# GarageMote.net
KiCad netlist of a schematic drawn in EAGLE
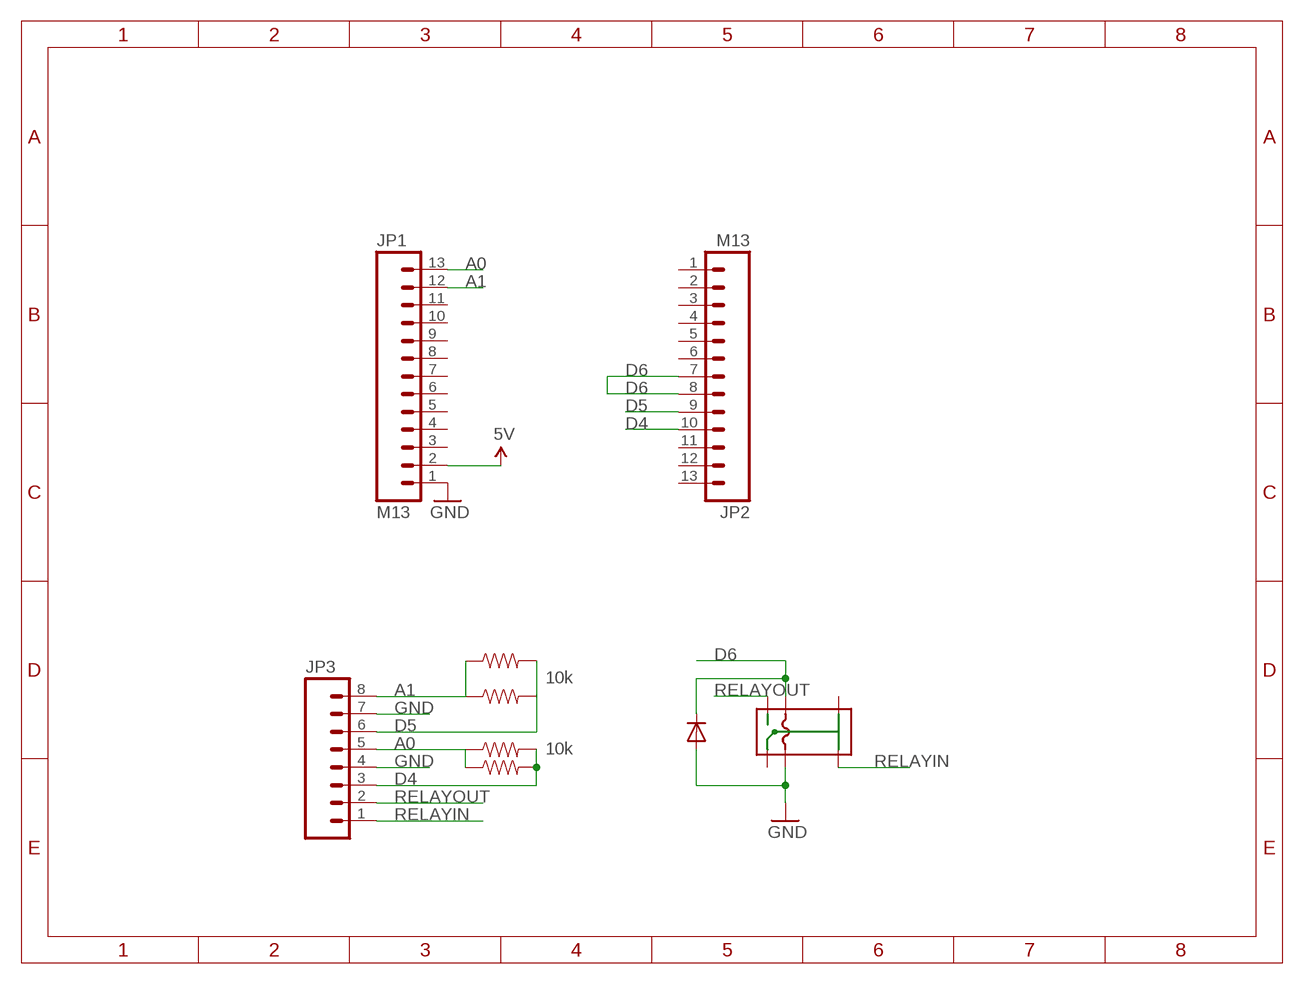
[diagram p0: schematic, sheet 1]

(export (version "E")
  (design (tool "Eeschema 10.0.6"))
  (components
    (comp (ref "1N4001")
      (value "DIODEUPRIGHT")
      (footprint "eagle-import:DIODE_UPRIGHT")
      (libsource (lib "eagle-import") (part "DIODEUPRIGHT"))
    )
    (comp (ref "JP1")
      (value "M13")
      (footprint "eagle-import:1X13")
      (libsource (lib "eagle-import") (part "M13"))
    )
    (comp (ref "JP2")
      (value "M13")
      (footprint "eagle-import:1X13")
      (libsource (lib "eagle-import") (part "M13"))
    )
    (comp (ref "JP3")
      (value "M081X08")
      (footprint "eagle-import:1X08")
      (libsource (lib "eagle-import") (part "M081X08"))
    )
    (comp (ref "JRC-2F")
      (value "JRC-23F")
      (footprint "eagle-import:JRC-23F")
      (libsource (lib "eagle-import") (part "JRC-23F"))
    )
    (comp (ref "R1")
      (value "10k")
      (footprint "eagle-import:0603-RES")
      (libsource (lib "eagle-import") (part "RESISTOR0603-RES"))
    )
    (comp (ref "R2")
      (value "10k")
      (footprint "eagle-import:0603-RES")
      (libsource (lib "eagle-import") (part "RESISTOR0603-RES"))
    )
    (comp (ref "R3")
      (value "RESISTOR1/4W")
      (footprint "eagle-import:AXIAL-1_4W")
      (libsource (lib "eagle-import") (part "RESISTOR1/4W"))
    )
    (comp (ref "R4")
      (value "RESISTOR1/4W")
      (footprint "eagle-import:AXIAL-1_4W")
      (libsource (lib "eagle-import") (part "RESISTOR1/4W"))
    )
  )
  (nets
    (net (code "1") (name "/A0") (class "Default")
      (node (ref "JP1") (pin "13") (pinfunction "13_13") (pintype "passive"))
      (node (ref "JP3") (pin "5") (pinfunction "5_5") (pintype "passive"))
      (node (ref "R1") (pin "1") (pinfunction "1_1") (pintype "passive"))
      (node (ref "R3") (pin "P$1") (pinfunction "1_P$1") (pintype "passive"))
    )
    (net (code "2") (name "/A1") (class "Default")
      (node (ref "JP1") (pin "12") (pinfunction "12_12") (pintype "passive"))
      (node (ref "JP3") (pin "8") (pinfunction "8_8") (pintype "passive"))
      (node (ref "R2") (pin "1") (pinfunction "1_1") (pintype "passive"))
      (node (ref "R4") (pin "P$1") (pinfunction "1_P$1") (pintype "passive"))
    )
    (net (code "3") (name "/D4") (class "Default")
      (node (ref "JP2") (pin "10") (pinfunction "10_10") (pintype "passive"))
      (node (ref "JP3") (pin "3") (pinfunction "3_3") (pintype "passive"))
      (node (ref "R1") (pin "2") (pinfunction "2_2") (pintype "passive"))
      (node (ref "R3") (pin "P$2") (pinfunction "2_P$2") (pintype "passive"))
    )
    (net (code "4") (name "/D5") (class "Default")
      (node (ref "JP2") (pin "9") (pinfunction "9_9") (pintype "passive"))
      (node (ref "JP3") (pin "6") (pinfunction "6_6") (pintype "passive"))
      (node (ref "R2") (pin "2") (pinfunction "2_2") (pintype "passive"))
      (node (ref "R4") (pin "P$2") (pinfunction "2_P$2") (pintype "passive"))
    )
    (net (code "5") (name "/D6") (class "Default")
      (node (ref "1N4001") (pin "CATHODE_MINUS") (pinfunction "CATHODE_MINUS_CATHODE_MINUS") (pintype "passive"))
      (node (ref "JP2") (pin "7") (pinfunction "7_7") (pintype "passive"))
      (node (ref "JP2") (pin "8") (pinfunction "8_8") (pintype "passive"))
      (node (ref "JRC-2F") (pin "COIL1") (pinfunction "COIL1_COIL1") (pintype "bidirectional"))
    )
    (net (code "6") (name "/RELAYIN") (class "Default")
      (node (ref "JP3") (pin "1") (pinfunction "1_1") (pintype "passive"))
      (node (ref "JRC-2F") (pin "COM2") (pinfunction "COM2_COM2") (pintype "bidirectional"))
    )
    (net (code "7") (name "/RELAYOUT") (class "Default")
      (node (ref "JP3") (pin "2") (pinfunction "2_2") (pintype "passive"))
      (node (ref "JRC-2F") (pin "SW1") (pinfunction "SW1_SW1") (pintype "bidirectional"))
    )
    (net (code "8") (name "5V") (class "Default")
      (node (ref "JP1") (pin "2") (pinfunction "2_2") (pintype "passive"))
    )
    (net (code "9") (name "GND") (class "Default")
      (node (ref "1N4001") (pin "ANODE_PLUS") (pinfunction "ANODE_PLUS_ANODE_PLUS") (pintype "passive"))
      (node (ref "JP1") (pin "1") (pinfunction "1_1") (pintype "passive"))
      (node (ref "JP3") (pin "4") (pinfunction "4_4") (pintype "passive"))
      (node (ref "JP3") (pin "7") (pinfunction "7_7") (pintype "passive"))
      (node (ref "JRC-2F") (pin "COIL2") (pinfunction "COIL2_COIL2") (pintype "bidirectional"))
    )
    (net (code "10") (name "unconnected-(JP1-Pad3)") (class "Default")
      (node (ref "JP1") (pin "3") (pinfunction "3_3") (pintype "passive"))
    )
    (net (code "11") (name "unconnected-(JP1-Pad4)") (class "Default")
      (node (ref "JP1") (pin "4") (pinfunction "4_4") (pintype "passive"))
    )
    (net (code "12") (name "unconnected-(JP1-Pad5)") (class "Default")
      (node (ref "JP1") (pin "5") (pinfunction "5_5") (pintype "passive"))
    )
    (net (code "13") (name "unconnected-(JP1-Pad6)") (class "Default")
      (node (ref "JP1") (pin "6") (pinfunction "6_6") (pintype "passive"))
    )
    (net (code "14") (name "unconnected-(JP1-Pad7)") (class "Default")
      (node (ref "JP1") (pin "7") (pinfunction "7_7") (pintype "passive"))
    )
    (net (code "15") (name "unconnected-(JP1-Pad8)") (class "Default")
      (node (ref "JP1") (pin "8") (pinfunction "8_8") (pintype "passive"))
    )
    (net (code "16") (name "unconnected-(JP1-Pad9)") (class "Default")
      (node (ref "JP1") (pin "9") (pinfunction "9_9") (pintype "passive"))
    )
    (net (code "17") (name "unconnected-(JP1-Pad10)") (class "Default")
      (node (ref "JP1") (pin "10") (pinfunction "10_10") (pintype "passive"))
    )
    (net (code "18") (name "unconnected-(JP1-Pad11)") (class "Default")
      (node (ref "JP1") (pin "11") (pinfunction "11_11") (pintype "passive"))
    )
    (net (code "19") (name "unconnected-(JP2-Pad1)") (class "Default")
      (node (ref "JP2") (pin "1") (pinfunction "1_1") (pintype "passive"))
    )
    (net (code "20") (name "unconnected-(JP2-Pad2)") (class "Default")
      (node (ref "JP2") (pin "2") (pinfunction "2_2") (pintype "passive"))
    )
    (net (code "21") (name "unconnected-(JP2-Pad3)") (class "Default")
      (node (ref "JP2") (pin "3") (pinfunction "3_3") (pintype "passive"))
    )
    (net (code "22") (name "unconnected-(JP2-Pad4)") (class "Default")
      (node (ref "JP2") (pin "4") (pinfunction "4_4") (pintype "passive"))
    )
    (net (code "23") (name "unconnected-(JP2-Pad5)") (class "Default")
      (node (ref "JP2") (pin "5") (pinfunction "5_5") (pintype "passive"))
    )
    (net (code "24") (name "unconnected-(JP2-Pad6)") (class "Default")
      (node (ref "JP2") (pin "6") (pinfunction "6_6") (pintype "passive"))
    )
    (net (code "25") (name "unconnected-(JP2-Pad11)") (class "Default")
      (node (ref "JP2") (pin "11") (pinfunction "11_11") (pintype "passive"))
    )
    (net (code "26") (name "unconnected-(JP2-Pad12)") (class "Default")
      (node (ref "JP2") (pin "12") (pinfunction "12_12") (pintype "passive"))
    )
    (net (code "27") (name "unconnected-(JP2-Pad13)") (class "Default")
      (node (ref "JP2") (pin "13") (pinfunction "13_13") (pintype "passive"))
    )
    (net (code "28") (name "unconnected-(JRC-2F-PadCOM1)") (class "Default")
      (node (ref "JRC-2F") (pin "COM1") (pinfunction "COM1_COM1") (pintype "bidirectional"))
    )
    (net (code "29") (name "unconnected-(JRC-2F-PadSW2)") (class "Default")
      (node (ref "JRC-2F") (pin "SW2") (pinfunction "SW2_SW2") (pintype "bidirectional"))
    )
  )
)
